# Ethernet.net
KiCad netlist of a schematic drawn in Altium Designer
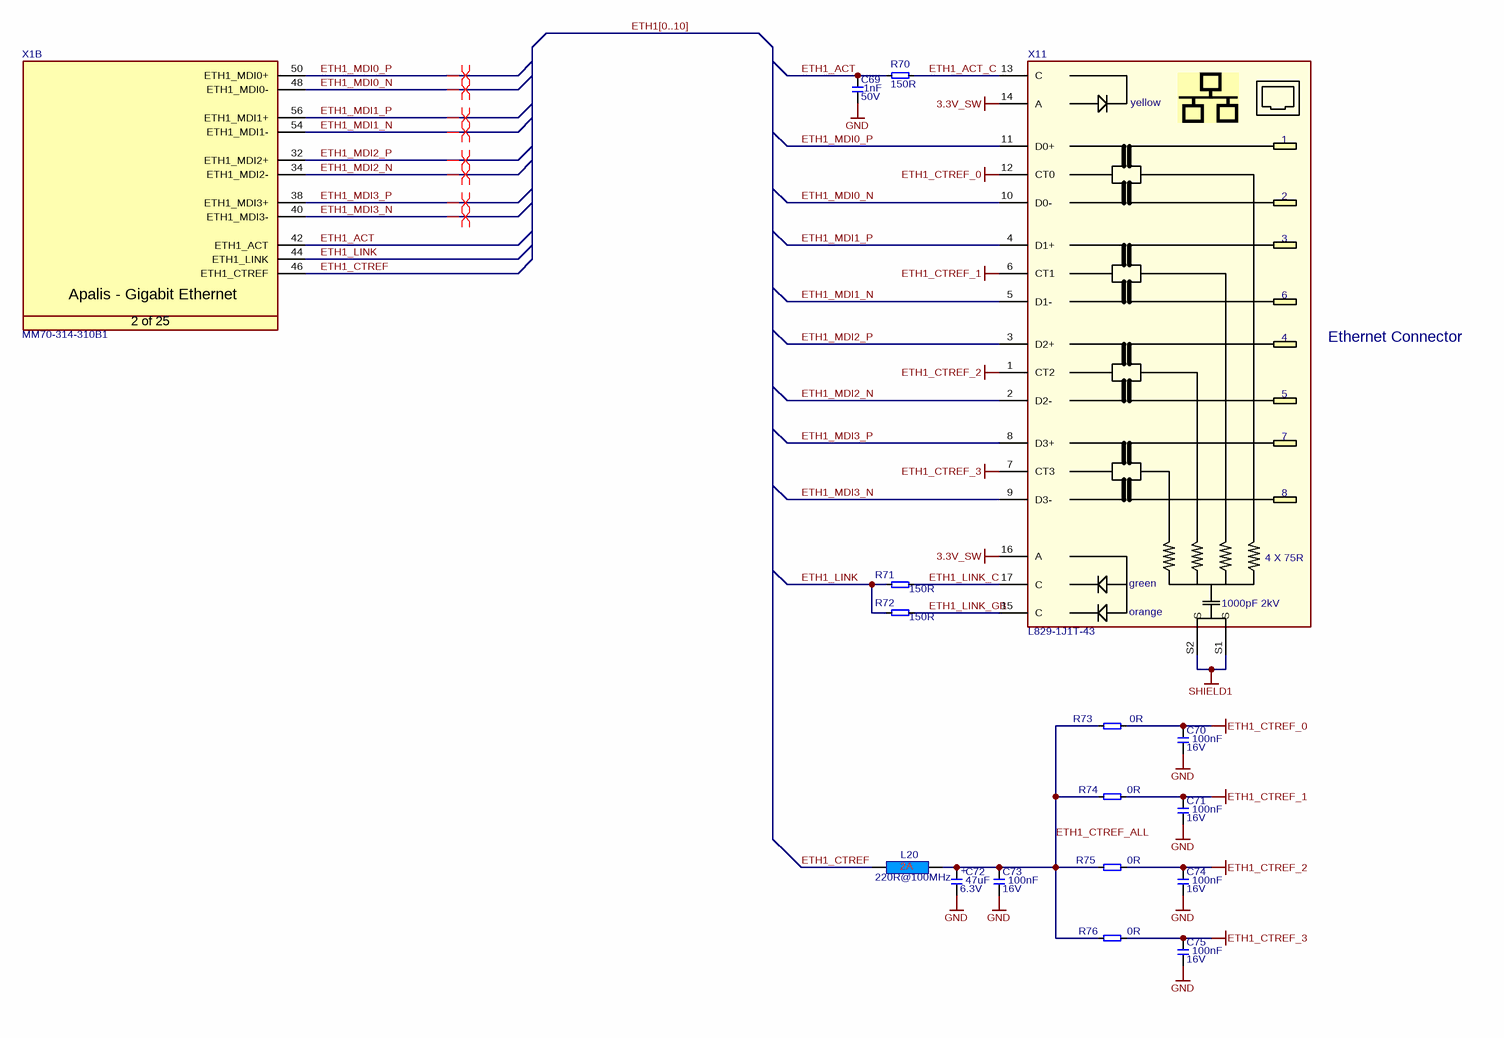
[diagram p0: Ethernet.SchDoc]

(export (version "E")
  (design (tool "Eeschema 10.0.6"))
  (components
    (comp (ref "C69")
      (value "1nF")
      (footprint "CAPC1005X60N")
      (description "Capacitor Ceramic X7R 1nF 50V 10% 0402")
      (fields (field (name "TOLERANCE") "10%") (field (name "RATING") "50V"))
      (libsource (lib "Ixora") (part "C-X7R-1nF-50V-10%-0402"))
    )
    (comp (ref "C70")
      (value "100nF")
      (footprint "CAPC1005X60N")
      (description "Capacitor Ceramic X7R 100nF 16V 10% 0402")
      (fields (field (name "TOLERANCE") "10%") (field (name "RATING") "16V"))
      (libsource (lib "Ixora") (part "C-X7R-100nF-16V-10%-0402"))
    )
    (comp (ref "C71")
      (value "100nF")
      (footprint "CAPC1005X60N")
      (description "Capacitor Ceramic X7R 100nF 16V 10% 0402")
      (fields (field (name "TOLERANCE") "10%") (field (name "RATING") "16V"))
      (libsource (lib "Ixora") (part "C-X7R-100nF-16V-10%-0402"))
    )
    (comp (ref "C72")
      (value "47uF")
      (footprint "T_CAPMP3216X180N")
      (description "Capacitor TA 47uF 6.3V 20% 3216")
      (fields (field (name "TOLERANCE") "20%") (field (name "RATING") "6.3V"))
      (libsource (lib "Ixora") (part "C-TA-47uF-6.3V-20%-3216"))
    )
    (comp (ref "C73")
      (value "100nF")
      (footprint "CAPC1005X60N")
      (description "Capacitor Ceramic X7R 100nF 16V 10% 0402")
      (fields (field (name "TOLERANCE") "10%") (field (name "RATING") "16V"))
      (libsource (lib "Ixora") (part "C-X7R-100nF-16V-10%-0402"))
    )
    (comp (ref "C74")
      (value "100nF")
      (footprint "CAPC1005X60N")
      (description "Capacitor Ceramic X7R 100nF 16V 10% 0402")
      (fields (field (name "TOLERANCE") "10%") (field (name "RATING") "16V"))
      (libsource (lib "Ixora") (part "C-X7R-100nF-16V-10%-0402"))
    )
    (comp (ref "C75")
      (value "100nF")
      (footprint "CAPC1005X60N")
      (description "Capacitor Ceramic X7R 100nF 16V 10% 0402")
      (fields (field (name "TOLERANCE") "10%") (field (name "RATING") "16V"))
      (libsource (lib "Ixora") (part "C-X7R-100nF-16V-10%-0402"))
    )
    (comp (ref "L20")
      (value "220R@100MHz")
      (footprint "INDC1608X95N")
      (description "220R@100MHz 2A EMI FILTER")
      (fields (field (name "TOLERANCE") "25%"))
      (libsource (lib "Ixora") (part "L-220R@100MHz-2A-25%-0603"))
    )
    (comp (ref "R70")
      (value "150R")
      (footprint "RESC1005X40N")
      (description "Resistor 150 ohm 63mW 1% 0402")
      (fields (field (name "TOLERANCE") "1%"))
      (libsource (lib "Ixora") (part "R-150R-63mW-1%-0402"))
    )
    (comp (ref "R71")
      (value "150R")
      (footprint "RESC1005X40N")
      (description "Resistor 150 ohm 63mW 1% 0402")
      (fields (field (name "TOLERANCE") "1%"))
      (libsource (lib "Ixora") (part "R-150R-63mW-1%-0402"))
    )
    (comp (ref "R72")
      (value "150R")
      (footprint "RESC1005X40N")
      (description "Resistor 150 ohm 63mW 1% 0402")
      (fields (field (name "TOLERANCE") "1%"))
      (libsource (lib "Ixora") (part "R-150R-63mW-1%-0402"))
    )
    (comp (ref "R73")
      (value "0R")
      (footprint "RESC1005X40N")
      (description "Resistor 0 ohm 63mW 1% 0402")
      (fields (field (name "TOLERANCE") "1%"))
      (libsource (lib "Ixora") (part "R-0R-63mW-1%-0402"))
    )
    (comp (ref "R74")
      (value "0R")
      (footprint "RESC1005X40N")
      (description "Resistor 0 ohm 63mW 1% 0402")
      (fields (field (name "TOLERANCE") "1%"))
      (libsource (lib "Ixora") (part "R-0R-63mW-1%-0402"))
    )
    (comp (ref "R75")
      (value "0R")
      (footprint "RESC1005X40N")
      (description "Resistor 0 ohm 63mW 1% 0402")
      (fields (field (name "TOLERANCE") "1%"))
      (libsource (lib "Ixora") (part "R-0R-63mW-1%-0402"))
    )
    (comp (ref "R76")
      (value "0R")
      (footprint "RESC1005X40N")
      (description "Resistor 0 ohm 63mW 1% 0402")
      (fields (field (name "TOLERANCE") "1%"))
      (libsource (lib "Ixora") (part "R-0R-63mW-1%-0402"))
    )
    (comp (ref "X1")
      (value "CON-JAE-MM70-314-310B1-314-0.5mm")
      (footprint "T_JAE_MM70-314-310B1")
      (description "MXM3 Connector")
      (fields (field (name "MANUFACTURER PART NO.") "MM70-314-310B1"))
      (libsource (lib "Ixora") (part "CON-JAE-MM70-314-310B1-314-0.5mm"))
    )
    (comp (ref "X11")
      (value "L829-1J1T-43")
      (footprint "T_BEL_L829-1J1T-43")
      (description "Low profile 10/100/1G Mag Jack")
      (fields (field (name "MANUFACTURER PART NO.") "L829-1J1T-43"))
      (libsource (lib "Ixora") (part "CON-BEL-L829-1J1T-43"))
    )
  )
  (nets
    (net (code "13") (name "/ETH1_ACT") (class "Default")
      (node (ref "C69") (pin "2") (pinfunction "2_2") (pintype "passive"))
      (node (ref "R70") (pin "1") (pinfunction "1_1") (pintype "passive"))
      (node (ref "X1") (pin "42") (pinfunction "ETH1_ACT_42") (pintype "passive"))
    )
    (net (code "14") (name "/ETH1_ACT_C") (class "Default")
      (node (ref "R70") (pin "2") (pinfunction "2_2") (pintype "passive"))
      (node (ref "X11") (pin "13") (pinfunction "C_13") (pintype "passive"))
    )
    (net (code "15") (name "/ETH1_CTREF") (class "Default")
      (node (ref "L20") (pin "1") (pinfunction "1_1") (pintype "passive"))
      (node (ref "X1") (pin "46") (pinfunction "ETH1_CTREF_46") (pintype "passive"))
    )
    (net (code "16") (name "/ETH1_CTREF_ALL") (class "Default")
      (node (ref "C72") (pin "1") (pinfunction "1_1") (pintype "passive"))
      (node (ref "C73") (pin "2") (pinfunction "2_2") (pintype "passive"))
      (node (ref "L20") (pin "2") (pinfunction "2_2") (pintype "passive"))
      (node (ref "R73") (pin "1") (pinfunction "1_1") (pintype "passive"))
      (node (ref "R74") (pin "1") (pinfunction "1_1") (pintype "passive"))
      (node (ref "R75") (pin "1") (pinfunction "1_1") (pintype "passive"))
      (node (ref "R76") (pin "1") (pinfunction "1_1") (pintype "passive"))
    )
    (net (code "17") (name "/ETH1_LINK") (class "Default")
      (node (ref "R71") (pin "1") (pinfunction "1_1") (pintype "passive"))
      (node (ref "R72") (pin "1") (pinfunction "1_1") (pintype "passive"))
      (node (ref "X1") (pin "44") (pinfunction "ETH1_LINK_44") (pintype "passive"))
    )
    (net (code "18") (name "/ETH1_LINK_C") (class "Default")
      (node (ref "R71") (pin "2") (pinfunction "2_2") (pintype "passive"))
      (node (ref "X11") (pin "17") (pinfunction "C_17") (pintype "passive"))
    )
    (net (code "19") (name "/ETH1_LINK_GB") (class "Default")
      (node (ref "R72") (pin "2") (pinfunction "2_2") (pintype "passive"))
      (node (ref "X11") (pin "15") (pinfunction "C_15") (pintype "passive"))
    )
    (net (code "20") (name "/ETH1_MDI0_N") (class "Default")
      (node (ref "X1") (pin "48") (pinfunction "ETH1_MDI0-_48") (pintype "passive"))
      (node (ref "X11") (pin "10") (pinfunction "D0-_10") (pintype "passive"))
    )
    (net (code "21") (name "/ETH1_MDI0_P") (class "Default")
      (node (ref "X1") (pin "50") (pinfunction "ETH1_MDI0+_50") (pintype "passive"))
      (node (ref "X11") (pin "11") (pinfunction "D0+_11") (pintype "passive"))
    )
    (net (code "22") (name "/ETH1_MDI1_N") (class "Default")
      (node (ref "X1") (pin "54") (pinfunction "ETH1_MDI1-_54") (pintype "passive"))
      (node (ref "X11") (pin "5") (pinfunction "D1-_5") (pintype "passive"))
    )
    (net (code "23") (name "/ETH1_MDI1_P") (class "Default")
      (node (ref "X1") (pin "56") (pinfunction "ETH1_MDI1+_56") (pintype "passive"))
      (node (ref "X11") (pin "4") (pinfunction "D1+_4") (pintype "passive"))
    )
    (net (code "24") (name "/ETH1_MDI2_N") (class "Default")
      (node (ref "X1") (pin "34") (pinfunction "ETH1_MDI2-_34") (pintype "passive"))
      (node (ref "X11") (pin "2") (pinfunction "D2-_2") (pintype "passive"))
    )
    (net (code "25") (name "/ETH1_MDI2_P") (class "Default")
      (node (ref "X1") (pin "32") (pinfunction "ETH1_MDI2+_32") (pintype "passive"))
      (node (ref "X11") (pin "3") (pinfunction "D2+_3") (pintype "passive"))
    )
    (net (code "26") (name "/ETH1_MDI3_N") (class "Default")
      (node (ref "X1") (pin "40") (pinfunction "ETH1_MDI3-_40") (pintype "passive"))
      (node (ref "X11") (pin "9") (pinfunction "D3-_9") (pintype "passive"))
    )
    (net (code "27") (name "/ETH1_MDI3_P") (class "Default")
      (node (ref "X1") (pin "38") (pinfunction "ETH1_MDI3+_38") (pintype "passive"))
      (node (ref "X11") (pin "8") (pinfunction "D3+_8") (pintype "passive"))
    )
    (net (code "28") (name "3.3V_SW") (class "Default")
      (node (ref "X11") (pin "14") (pinfunction "A_14") (pintype "passive"))
      (node (ref "X11") (pin "16") (pinfunction "A_16") (pintype "passive"))
    )
    (net (code "29") (name "ETH1_CTREF_0") (class "Default")
      (node (ref "C70") (pin "2") (pinfunction "2_2") (pintype "passive"))
      (node (ref "R73") (pin "2") (pinfunction "2_2") (pintype "passive"))
      (node (ref "X11") (pin "12") (pinfunction "CT0_12") (pintype "passive"))
    )
    (net (code "30") (name "ETH1_CTREF_1") (class "Default")
      (node (ref "C71") (pin "2") (pinfunction "2_2") (pintype "passive"))
      (node (ref "R74") (pin "2") (pinfunction "2_2") (pintype "passive"))
      (node (ref "X11") (pin "6") (pinfunction "CT1_6") (pintype "passive"))
    )
    (net (code "31") (name "ETH1_CTREF_2") (class "Default")
      (node (ref "C74") (pin "2") (pinfunction "2_2") (pintype "passive"))
      (node (ref "R75") (pin "2") (pinfunction "2_2") (pintype "passive"))
      (node (ref "X11") (pin "1") (pinfunction "CT2_1") (pintype "passive"))
    )
    (net (code "32") (name "ETH1_CTREF_3") (class "Default")
      (node (ref "C75") (pin "2") (pinfunction "2_2") (pintype "passive"))
      (node (ref "R76") (pin "2") (pinfunction "2_2") (pintype "passive"))
      (node (ref "X11") (pin "7") (pinfunction "CT3_7") (pintype "passive"))
    )
    (net (code "33") (name "GND") (class "Default")
      (node (ref "C69") (pin "1") (pinfunction "1_1") (pintype "passive"))
      (node (ref "C70") (pin "1") (pinfunction "1_1") (pintype "passive"))
      (node (ref "C71") (pin "1") (pinfunction "1_1") (pintype "passive"))
      (node (ref "C72") (pin "2") (pinfunction "2_2") (pintype "passive"))
      (node (ref "C73") (pin "1") (pinfunction "1_1") (pintype "passive"))
      (node (ref "C74") (pin "1") (pinfunction "1_1") (pintype "passive"))
      (node (ref "C75") (pin "1") (pinfunction "1_1") (pintype "passive"))
    )
    (net (code "34") (name "SHIELD1") (class "Default")
      (node (ref "X11") (pin "S1") (pinfunction "S_S1") (pintype "passive"))
      (node (ref "X11") (pin "S2") (pinfunction "S_S2") (pintype "passive"))
    )
  )
)
